# MSXII_SteeringWheelBoard.net
KiCad netlist of a schematic drawn in Altium Designer
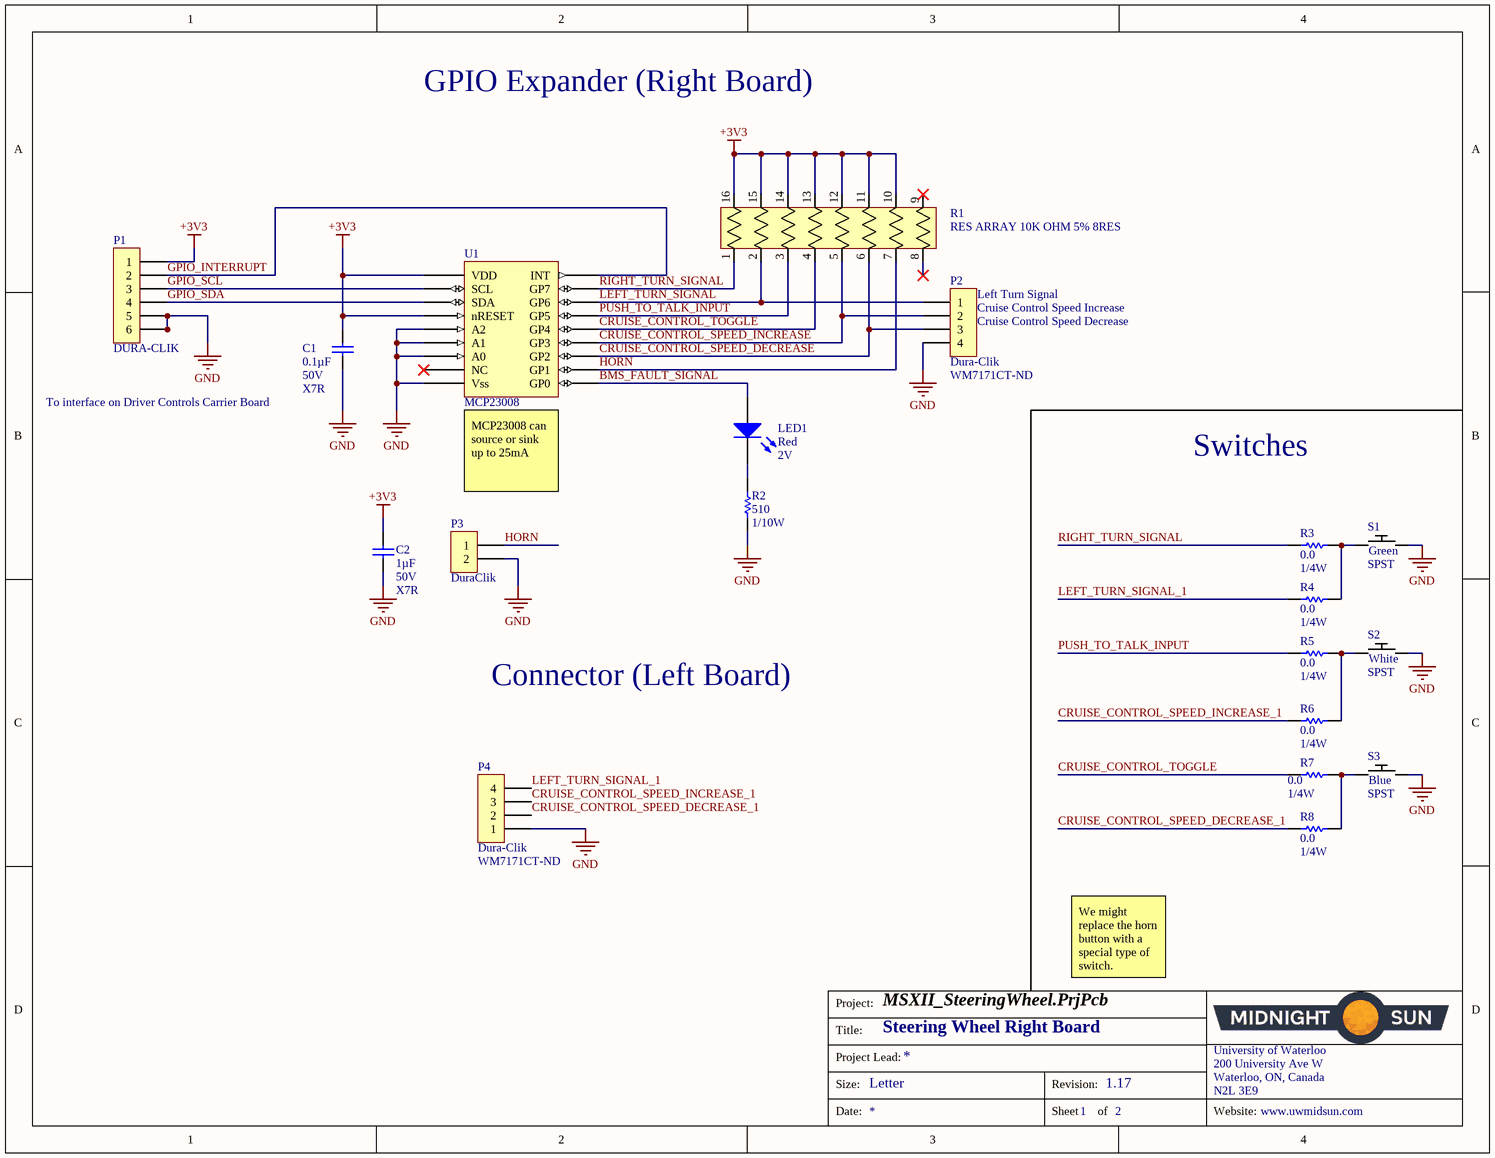
[diagram p0: MSXII_SteeringWheelBoard.SchDoc]

(export (version "E")
  (design (tool "Eeschema 10.0.6"))
  (components
    (comp (ref "C1")
      (value "CAP CER 0.1UF 50V 10% X7R 0603")
      (footprint "CAP, 0603")
      (description "0.10µF ±10% 50V Ceramic Capacitor X7R 0603 (1608 Metric)")
      (fields
        (field (name "TOLERANCE") "±10%")
        (field (name "CAPACITANCE") "0.1µF")
        (field (name "VOLTAGE") "50V")
        (field (name "TEMPERATURE COEFFICIENT") "X7R")
      )
      (libsource (lib "Schematic Diagrams") (part "CAP CER 0.1UF 50V 10% X7R 0603"))
    )
    (comp (ref "C2")
      (value "CAP CER 1UF 50V 10% X7R 0603")
      (footprint "CAP, 0603")
      (description "1µF ±10% 50V Ceramic Capacitor X7R 0603 (1608 Metric)")
      (fields
        (field (name "TOLERANCE") "±10%")
        (field (name "CAPACITANCE") "1µF")
        (field (name "VOLTAGE") "50V")
        (field (name "TEMPERATURE COEFFICIENT") "X7R")
      )
      (libsource (lib "Schematic Diagrams") (part "CAP CER 1UF 50V 10% X7R 0603"))
    )
    (comp (ref "LED1")
      (value "LED RED CLEAR 2V 0603")
      (footprint "LED_0603")
      (description "Red 631nm LED Indication - Discrete 2V 0603 (1608 Metric)")
      (fields
        (field (name "MANUFACTURER") "Wurth Electronics Inc.")
        (field (name "MANUFACTURER PART NUMBER") "150060RS75000")
        (field (name "COLOR") "Red")
        (field (name "VOLTAGE - FORWARD (VF) (TYP)") "2V")
      )
      (libsource (lib "Schematic Diagrams") (part "LED RED CLEAR 2V 0603"))
    )
    (comp (ref "P1")
      (value "DURA-CLIK")
      (footprint "CONN, 6POS Dura-Click")
      (description "6 Positions Header, Shrouded Connector 0.079\" (2.00mm) Surface Mount, Right Angle Tin")
      (fields
        (field (name "MANUFACTURER") "Molex, LLC")
        (field (name "MANUFACTURER PART NUMBER") "5023520600")
      )
      (libsource (lib "Schematic Diagrams") (part "CONN 6POS DURA-CLIK 0.079{dblquote} RGT"))
    )
    (comp (ref "P2")
      (value "Dura-Clik")
      (footprint "CONN, 4POS Dura-Click")
      (description "4 Positions Header Connector 0.079\" (2.00mm) Surface Mount, Right Angle Tin")
      (fields
        (field (name "MANUFACTURER") "Molex, LLC")
        (field (name "MANUFACTURER PART NUMBER") "5023520400")
        (field (name "SUPPLIER PART NUMBER 1") "WM7171CT-ND")
      )
      (libsource (lib "") (part "CONN 4POS DURA-CLIK 0.079{dblquote} RGT_1"))
    )
    (comp (ref "P3")
      (value "CONN 2POS DURA-CLIK 0.079\"")
      (footprint "CONN, 2POS Dura-Click")
      (description "2 Positions Header, Shrouded Connector 0.079\" (2.00mm) Surface Mount, Right Angle Tin")
      (fields (field (name "SERIES") "DuraClik"))
      (libsource (lib "Schematic Diagrams") (part "CONN 2POS DURA-CLIK 0.079{dblquote}"))
    )
    (comp (ref "P4")
      (value "Dura-Clik")
      (footprint "CONN, 4POS Dura-Click")
      (description "4 Positions Header Connector 0.079\" (2.00mm) Surface Mount, Right Angle Tin")
      (fields
        (field (name "MANUFACTURER") "Molex, LLC")
        (field (name "MANUFACTURER PART NUMBER") "5023520400")
        (field (name "SUPPLIER PART NUMBER 1") "WM7171CT-ND")
      )
      (libsource (lib "Schematic Diagrams") (part "CONN 4POS DURA-CLIK 0.079{dblquote} RGT"))
    )
    (comp (ref "R1")
      (value "RES ARRAY 10K OHM 5% 8RES")
      (footprint "RES ARRAY, 8 POS 1506")
      (description "RES ARRAY SMD 10K 5% 62.5mW 1506")
      (fields
        (field (name "MANUFACTURER_PART_NUMBER") "EXB-2HV103JV")
        (field (name "MANUFACTURER") "Panasonic Electronic Components")
        (field (name "COPYRIGHT") "Copyright (C) 2015 Accelerated Designs. All rights reserved")
      )
      (libsource (lib "Schematic Diagrams") (part "RES ARRAY 10K OHM 5% 8RES EXB-2HV103JV"))
    )
    (comp (ref "R2")
      (value "RES 510 OHM 5% 1/10W 0603")
      (footprint "RES, 0603")
      (description "RES SMD 510 OHM 5% 1/10W 0603")
      (fields
        (field (name "TOLERANCE") "±5%")
        (field (name "RESISTANCE") "510")
        (field (name "POWER") "1/10W")
      )
      (libsource (lib "Schematic Diagrams") (part "RES 510 OHM 5% 1/10W 0603"))
    )
    (comp (ref "R3")
      (value "RES 0.0 OHM 1/4W 0603")
      (footprint "RES, 0603")
      (description "RES SMD 0.0 OHM JUMPER 1/4W 0603")
      (fields (field (name "RESISTANCE") "0.0") (field (name "POWER (WATTS)") "1/4W"))
      (libsource (lib "Schematic Diagrams") (part "RES 0.0 OHM 1/4W 0603"))
    )
    (comp (ref "R4")
      (value "RES 0.0 OHM 1/4W 0603")
      (footprint "RES, 0603")
      (description "RES SMD 0.0 OHM JUMPER 1/4W 0603")
      (fields (field (name "RESISTANCE") "0.0") (field (name "POWER (WATTS)") "1/4W"))
      (libsource (lib "Schematic Diagrams") (part "RES 0.0 OHM 1/4W 0603"))
    )
    (comp (ref "R5")
      (value "RES 0.0 OHM 1/4W 0603")
      (footprint "RES, 0603")
      (description "RES SMD 0.0 OHM JUMPER 1/4W 0603")
      (fields (field (name "RESISTANCE") "0.0") (field (name "POWER (WATTS)") "1/4W"))
      (libsource (lib "Schematic Diagrams") (part "RES 0.0 OHM 1/4W 0603"))
    )
    (comp (ref "R6")
      (value "RES 0.0 OHM 1/4W 0603")
      (footprint "RES, 0603")
      (description "RES SMD 0.0 OHM JUMPER 1/4W 0603")
      (fields (field (name "RESISTANCE") "0.0") (field (name "POWER (WATTS)") "1/4W"))
      (libsource (lib "Schematic Diagrams") (part "RES 0.0 OHM 1/4W 0603"))
    )
    (comp (ref "R7")
      (value "RES 0.0 OHM 1/4W 0603")
      (footprint "RES, 0603")
      (description "RES SMD 0.0 OHM JUMPER 1/4W 0603")
      (fields (field (name "RESISTANCE") "0.0") (field (name "POWER (WATTS)") "1/4W"))
      (libsource (lib "Schematic Diagrams") (part "RES 0.0 OHM 1/4W 0603"))
    )
    (comp (ref "R8")
      (value "RES 0.0 OHM 1/4W 0603")
      (footprint "RES, 0603")
      (description "RES SMD 0.0 OHM JUMPER 1/4W 0603")
      (fields (field (name "RESISTANCE") "0.0") (field (name "POWER (WATTS)") "1/4W"))
      (libsource (lib "Schematic Diagrams") (part "RES 0.0 OHM 1/4W 0603"))
    )
    (comp (ref "S1")
      (value "SPST")
      (footprint "SW SPST D6 SERIES GREEN")
      (description "Pushbutton Switch SPST-NO Keyswitch Through Hole D6 Series Green")
      (fields (field (name "MANUFACTURER") "C&K") (field (name "MANUFACTURER PART NUMBER") "D6R50 F1 LFS"))
      (libsource (lib "Schematic Diagrams") (part "SW SPST-NO 0.1A 32V D6 Series Green"))
    )
    (comp (ref "S2")
      (value "SPST")
      (footprint "SW SPST D6 SERIES WHITE")
      (description "Pushbutton Switch SPST-NO Keyswitch Through Hole D6 Series White")
      (fields (field (name "MANUFACTURER") "C&K") (field (name "MANUFACTURER PART NUMBER") "D6R00 F2 LFS"))
      (libsource (lib "Schematic Diagrams") (part "SW SPST-NO 0.1A 32V D6 Series White"))
    )
    (comp (ref "S3")
      (value "SPST")
      (footprint "SW SPST D6 SERIES BLUE")
      (description "Pushbutton Switch SPST-NO Keyswitch Through Hole D6 Series Blue")
      (fields (field (name "MANUFACTURER") "C&K") (field (name "MANUFACTURER PART NUMBER") "D6R60 F1 LFS"))
      (libsource (lib "Schematic Diagrams") (part "SW SPST-NO 0.1A 32V D6 Series Blue"))
    )
    (comp (ref "U1")
      (value "MCP23008")
      (footprint "IC 18SOIC")
      (description "MCP23008 I/O Expander 8B+1Int 18P SOIC")
      (fields
        (field (name "MANUFACTURER") "Microchip Technology")
        (field (name "MANUFACTURER PART NUMBER") "MCP23008T-E/SO")
      )
      (libsource (lib "Schematic Diagrams") (part "IC I/O EXPANDER I2C 8B 18SOIC"))
    )
  )
  (nets
    (net (code "1") (name "+3V3") (class "Default")
      (node (ref "C1") (pin "1") (pinfunction "1_1") (pintype "passive"))
      (node (ref "C2") (pin "1") (pinfunction "1_1") (pintype "passive"))
      (node (ref "P1") (pin "1") (pinfunction "1_1") (pintype "passive"))
      (node (ref "R1") (pin "10") (pinfunction "10_10") (pintype "passive"))
      (node (ref "R1") (pin "11") (pinfunction "11_11") (pintype "passive"))
      (node (ref "R1") (pin "12") (pinfunction "12_12") (pintype "passive"))
      (node (ref "R1") (pin "13") (pinfunction "13_13") (pintype "passive"))
      (node (ref "R1") (pin "14") (pinfunction "14_14") (pintype "passive"))
      (node (ref "R1") (pin "15") (pinfunction "15_15") (pintype "passive"))
      (node (ref "R1") (pin "16") (pinfunction "16_16") (pintype "passive"))
      (node (ref "U1") (pin "18") (pinfunction "VDD_18") (pintype "power_in"))
      (node (ref "U1") (pin "6") (pinfunction "nRESET_6") (pintype "input"))
    )
    (net (code "2") (name "/BMS_FAULT_SIGNAL") (class "Default")
      (node (ref "LED1") (pin "1") (pinfunction "A_1") (pintype "passive"))
      (node (ref "U1") (pin "10") (pinfunction "GP0_10") (pintype "bidirectional"))
    )
    (net (code "3") (name "/CRUISE_CONTROL_SPEED_DECREASE") (class "Default")
      (node (ref "P2") (pin "3") (pinfunction "3_3") (pintype "passive"))
      (node (ref "R1") (pin "6") (pinfunction "6_6") (pintype "passive"))
      (node (ref "U1") (pin "12") (pinfunction "GP2_12") (pintype "bidirectional"))
    )
    (net (code "4") (name "/CRUISE_CONTROL_SPEED_DECREASE_1") (class "Default")
      (node (ref "P4") (pin "2") (pinfunction "2_2") (pintype "passive"))
      (node (ref "R8") (pin "1") (pinfunction "1_1") (pintype "passive"))
    )
    (net (code "5") (name "/CRUISE_CONTROL_SPEED_INCREASE") (class "Default")
      (node (ref "P2") (pin "2") (pinfunction "2_2") (pintype "passive"))
      (node (ref "R1") (pin "5") (pinfunction "5_5") (pintype "passive"))
      (node (ref "U1") (pin "13") (pinfunction "GP3_13") (pintype "bidirectional"))
    )
    (net (code "6") (name "/CRUISE_CONTROL_SPEED_INCREASE_1") (class "Default")
      (node (ref "P4") (pin "3") (pinfunction "3_3") (pintype "passive"))
      (node (ref "R6") (pin "1") (pinfunction "1_1") (pintype "passive"))
    )
    (net (code "7") (name "/CRUISE_CONTROL_TOGGLE") (class "Default")
      (node (ref "R1") (pin "4") (pinfunction "4_4") (pintype "passive"))
      (node (ref "R7") (pin "1") (pinfunction "1_1") (pintype "passive"))
      (node (ref "U1") (pin "14") (pinfunction "GP4_14") (pintype "bidirectional"))
    )
    (net (code "8") (name "/GPIO_INTERRUPT") (class "Default")
      (node (ref "P1") (pin "2") (pinfunction "2_2") (pintype "passive"))
      (node (ref "U1") (pin "8") (pinfunction "INT_8") (pintype "output"))
    )
    (net (code "9") (name "/GPIO_SCL") (class "Default")
      (node (ref "P1") (pin "3") (pinfunction "3_3") (pintype "passive"))
      (node (ref "U1") (pin "1") (pinfunction "SCL_1") (pintype "bidirectional"))
    )
    (net (code "10") (name "/GPIO_SDA") (class "Default")
      (node (ref "P1") (pin "4") (pinfunction "4_4") (pintype "passive"))
      (node (ref "U1") (pin "2") (pinfunction "SDA_2") (pintype "bidirectional"))
    )
    (net (code "11") (name "/HORN") (class "Default")
      (node (ref "P3") (pin "1") (pinfunction "1_1") (pintype "passive"))
      (node (ref "R1") (pin "7") (pinfunction "7_7") (pintype "passive"))
      (node (ref "U1") (pin "11") (pinfunction "GP1_11") (pintype "bidirectional"))
    )
    (net (code "12") (name "/LEFT_TURN_SIGNAL") (class "Default")
      (node (ref "P2") (pin "1") (pinfunction "1_1") (pintype "passive"))
      (node (ref "R1") (pin "2") (pinfunction "2_2") (pintype "passive"))
      (node (ref "U1") (pin "16") (pinfunction "GP6_16") (pintype "bidirectional"))
    )
    (net (code "13") (name "/LEFT_TURN_SIGNAL_1") (class "Default")
      (node (ref "P4") (pin "4") (pinfunction "4_4") (pintype "passive"))
      (node (ref "R4") (pin "1") (pinfunction "1_1") (pintype "passive"))
    )
    (net (code "14") (name "/PUSH_TO_TALK_INPUT") (class "Default")
      (node (ref "R1") (pin "3") (pinfunction "3_3") (pintype "passive"))
      (node (ref "R5") (pin "1") (pinfunction "1_1") (pintype "passive"))
      (node (ref "U1") (pin "15") (pinfunction "GP5_15") (pintype "bidirectional"))
    )
    (net (code "15") (name "/RIGHT_TURN_SIGNAL") (class "Default")
      (node (ref "R1") (pin "1") (pinfunction "1_1") (pintype "passive"))
      (node (ref "R3") (pin "1") (pinfunction "1_1") (pintype "passive"))
      (node (ref "U1") (pin "17") (pinfunction "GP7_17") (pintype "bidirectional"))
    )
    (net (code "16") (name "GND") (class "Default")
      (node (ref "C1") (pin "2") (pinfunction "2_2") (pintype "passive"))
      (node (ref "C2") (pin "2") (pinfunction "2_2") (pintype "passive"))
      (node (ref "P1") (pin "5") (pinfunction "5_5") (pintype "passive"))
      (node (ref "P1") (pin "6") (pinfunction "6_6") (pintype "passive"))
      (node (ref "P2") (pin "4") (pinfunction "4_4") (pintype "passive"))
      (node (ref "P3") (pin "2") (pinfunction "2_2") (pintype "passive"))
      (node (ref "P4") (pin "1") (pinfunction "1_1") (pintype "passive"))
      (node (ref "R2") (pin "2") (pinfunction "2_2") (pintype "passive"))
      (node (ref "S1") (pin "2") (pinfunction "2_2") (pintype "passive"))
      (node (ref "S2") (pin "2") (pinfunction "2_2") (pintype "passive"))
      (node (ref "S3") (pin "2") (pinfunction "2_2") (pintype "passive"))
      (node (ref "U1") (pin "3") (pinfunction "A2_3") (pintype "input"))
      (node (ref "U1") (pin "4") (pinfunction "A1_4") (pintype "input"))
      (node (ref "U1") (pin "5") (pinfunction "A0_5") (pintype "input"))
      (node (ref "U1") (pin "9") (pinfunction "Vss_9") (pintype "power_in"))
    )
    (net (code "17") (name "Net-(LED1-K)") (class "Default")
      (node (ref "LED1") (pin "2") (pinfunction "K_2") (pintype "passive"))
      (node (ref "R2") (pin "1") (pinfunction "1_1") (pintype "passive"))
    )
    (net (code "18") (name "Net-(R3-Pad2)") (class "Default")
      (node (ref "R3") (pin "2") (pinfunction "2_2") (pintype "passive"))
      (node (ref "R4") (pin "2") (pinfunction "2_2") (pintype "passive"))
      (node (ref "S1") (pin "1") (pinfunction "1_1") (pintype "passive"))
    )
    (net (code "19") (name "Net-(R5-Pad2)") (class "Default")
      (node (ref "R5") (pin "2") (pinfunction "2_2") (pintype "passive"))
      (node (ref "R6") (pin "2") (pinfunction "2_2") (pintype "passive"))
      (node (ref "S2") (pin "1") (pinfunction "1_1") (pintype "passive"))
    )
    (net (code "20") (name "Net-(R7-Pad2)") (class "Default")
      (node (ref "R7") (pin "2") (pinfunction "2_2") (pintype "passive"))
      (node (ref "R8") (pin "2") (pinfunction "2_2") (pintype "passive"))
      (node (ref "S3") (pin "1") (pinfunction "1_1") (pintype "passive"))
    )
    (net (code "21") (name "unconnected-(R1-Pad8)") (class "Default")
      (node (ref "R1") (pin "8") (pinfunction "8_8") (pintype "passive+no_connect"))
    )
    (net (code "22") (name "unconnected-(R1-Pad9)") (class "Default")
      (node (ref "R1") (pin "9") (pinfunction "9_9") (pintype "passive+no_connect"))
    )
    (net (code "23") (name "unconnected-(U1-NC-Pad7)") (class "Default")
      (node (ref "U1") (pin "7") (pinfunction "NC_7") (pintype "passive+no_connect"))
    )
  )
)
